# lm3410-sepic-led-driver-15mm-mk-1.net
KiCad netlist of a schematic drawn in EAGLE
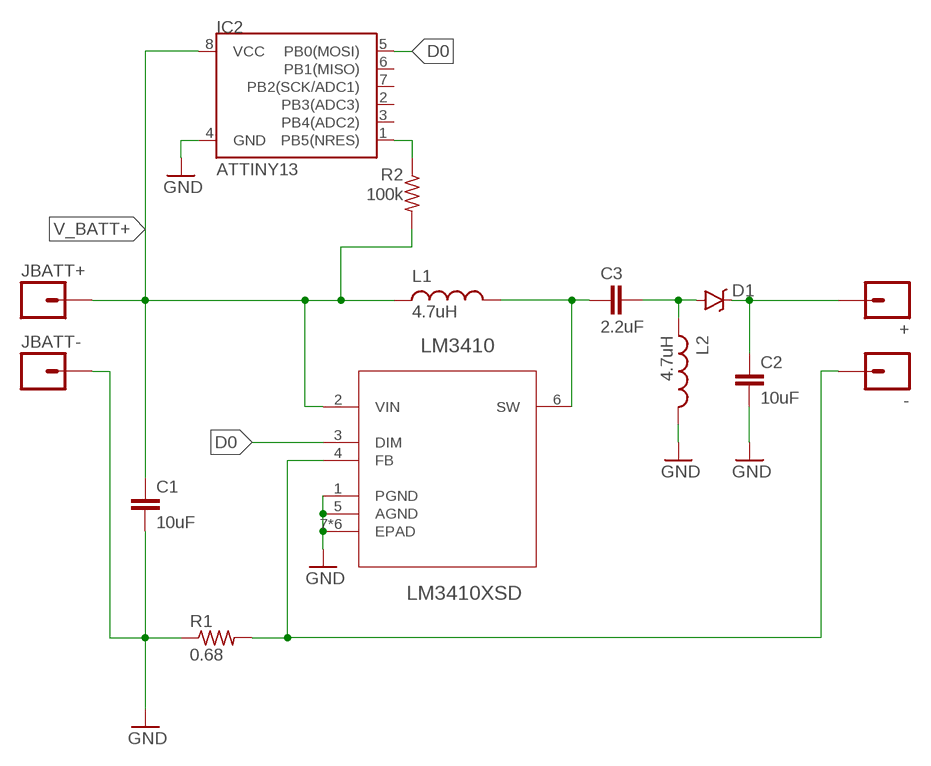
[diagram p0: schematic, sheet 1]

(export (version "E")
  (design (tool "Eeschema 10.0.6"))
  (components
    (comp (ref "+")
      (value "M01PTH-KIT")
      (footprint "eagle-import:1X01-KIT")
      (libsource (lib "eagle-import") (part "M01PTH-KIT"))
    )
    (comp (ref "-")
      (value "M01NOSILK-KIT")
      (footprint "eagle-import:1X01NS-KIT")
      (libsource (lib "eagle-import") (part "M01NOSILK-KIT"))
    )
    (comp (ref "C1")
      (value "10uF")
      (footprint "eagle-import:C0603")
      (libsource (lib "eagle-import") (part "CAPACITOR-CERAMICC0603"))
    )
    (comp (ref "C2")
      (value "10uF")
      (footprint "eagle-import:C0603")
      (libsource (lib "eagle-import") (part "CAPACITOR-CERAMICC0603"))
    )
    (comp (ref "C3")
      (value "2.2uF")
      (footprint "eagle-import:C0805")
      (libsource (lib "eagle-import") (part "CAPACITOR-CERAMICC0805"))
    )
    (comp (ref "D1")
      (value "BAT20J")
      (footprint "eagle-import:SOD-323")
      (libsource (lib "eagle-import") (part "DIODE-SCHOTTKYBAT20J"))
    )
    (comp (ref "IC2")
      (value "ATTINY13")
      (footprint "eagle-import:SO08")
      (libsource (lib "eagle-import") (part "ATTINY13SOIC"))
    )
    (comp (ref "JBATT+")
      (value "M01NOT-A-VIA-NOPE")
      (footprint "eagle-import:1X01_NOSILK_NOSTOP")
      (libsource (lib "eagle-import") (part "M01NOT-A-VIA-NOPE"))
    )
    (comp (ref "JBATT-")
      (value "M01NOT-A-VIA-NOPE")
      (footprint "eagle-import:1X01_NOSILK_NOSTOP")
      (libsource (lib "eagle-import") (part "M01NOT-A-VIA-NOPE"))
    )
    (comp (ref "L1")
      (value "4.7uH")
      (footprint "eagle-import:INDUCTOR_2X1.6MM")
      (libsource (lib "eagle-import") (part "INDUCTORIFSC-0806"))
    )
    (comp (ref "L2")
      (value "4.7uH")
      (footprint "eagle-import:INDUCTOR_2X1.6MM")
      (libsource (lib "eagle-import") (part "INDUCTORIFSC-0806"))
    )
    (comp (ref "LM3410")
      (value "LM3410XSD")
      (footprint "eagle-import:DFN300X300X80-7N")
      (libsource (lib "eagle-import") (part "LM3410XSD"))
    )
    (comp (ref "R1")
      (value "0.68")
      (footprint "eagle-import:R1206")
      (libsource (lib "eagle-import") (part "RESISTORR1206"))
    )
    (comp (ref "R2")
      (value "100k")
      (footprint "eagle-import:R0402")
      (libsource (lib "eagle-import") (part "RESISTORR0402"))
    )
  )
  (nets
    (net (code "1") (name "D0") (class "Default")
      (node (ref "IC2") (pin "5") (pinfunction "PB0(MOSI)_5") (pintype "bidirectional"))
      (node (ref "LM3410") (pin "3") (pinfunction "DIM_3") (pintype "input"))
    )
    (net (code "2") (name "GND") (class "Default")
      (node (ref "C1") (pin "2") (pinfunction "2_2") (pintype "passive"))
      (node (ref "C2") (pin "2") (pinfunction "2_2") (pintype "passive"))
      (node (ref "IC2") (pin "4") (pinfunction "GND_4") (pintype "bidirectional"))
      (node (ref "JBATT-") (pin "P$1") (pinfunction "1_P$1") (pintype "passive"))
      (node (ref "L2") (pin "P$2") (pinfunction "2_P$2") (pintype "passive"))
      (node (ref "LM3410") (pin "1") (pinfunction "PGND_1") (pintype "passive"))
      (node (ref "LM3410") (pin "5") (pinfunction "AGND_5") (pintype "passive"))
      (node (ref "LM3410") (pin "7") (pinfunction "EPAD_7") (pintype "passive"))
      (node (ref "LM3410") (pin "7@1") (pinfunction "EPAD_7@1") (pintype "passive"))
      (node (ref "LM3410") (pin "7@2") (pinfunction "EPAD_7@2") (pintype "passive"))
      (node (ref "LM3410") (pin "7@3") (pinfunction "EPAD_7@3") (pintype "passive"))
      (node (ref "LM3410") (pin "7@4") (pinfunction "EPAD_7@4") (pintype "passive"))
      (node (ref "LM3410") (pin "7@5") (pinfunction "EPAD_7@5") (pintype "passive"))
      (node (ref "R1") (pin "1") (pinfunction "1_1") (pintype "passive"))
    )
    (net (code "3") (name "Net-(+-Pad1)") (class "Default")
      (node (ref "+") (pin "1") (pinfunction "1_1") (pintype "passive"))
      (node (ref "C2") (pin "1") (pinfunction "1_1") (pintype "passive"))
      (node (ref "D1") (pin "C") (pinfunction "C_C") (pintype "passive"))
    )
    (net (code "4") (name "Net-(IC2-PB5(NRES))") (class "Default")
      (node (ref "IC2") (pin "1") (pinfunction "PB5(NRES)_1") (pintype "bidirectional"))
      (node (ref "R2") (pin "1") (pinfunction "1_1") (pintype "passive"))
    )
    (net (code "5") (name "Net-(L1-2)") (class "Default")
      (node (ref "C3") (pin "1") (pinfunction "1_1") (pintype "passive"))
      (node (ref "L1") (pin "P$2") (pinfunction "2_P$2") (pintype "passive"))
      (node (ref "LM3410") (pin "6") (pinfunction "SW_6") (pintype "output"))
    )
    (net (code "6") (name "Net-(L2-1)") (class "Default")
      (node (ref "C3") (pin "2") (pinfunction "2_2") (pintype "passive"))
      (node (ref "D1") (pin "A") (pinfunction "A_A") (pintype "passive"))
      (node (ref "L2") (pin "P$1") (pinfunction "1_P$1") (pintype "passive"))
    )
    (net (code "7") (name "Net-(LM3410-FB)") (class "Default")
      (node (ref "-") (pin "1") (pinfunction "1_1") (pintype "passive"))
      (node (ref "LM3410") (pin "4") (pinfunction "FB_4") (pintype "input"))
      (node (ref "R1") (pin "2") (pinfunction "2_2") (pintype "passive"))
    )
    (net (code "8") (name "V_BATT+") (class "Default")
      (node (ref "C1") (pin "1") (pinfunction "1_1") (pintype "passive"))
      (node (ref "IC2") (pin "8") (pinfunction "VCC_8") (pintype "bidirectional"))
      (node (ref "JBATT+") (pin "P$1") (pinfunction "1_P$1") (pintype "passive"))
      (node (ref "L1") (pin "P$1") (pinfunction "1_P$1") (pintype "passive"))
      (node (ref "LM3410") (pin "2") (pinfunction "VIN_2") (pintype "power_in"))
      (node (ref "R2") (pin "2") (pinfunction "2_2") (pintype "passive"))
    )
    (net (code "9") (name "unconnected-(IC2-PB1(MISO)-Pad6)") (class "Default")
      (node (ref "IC2") (pin "6") (pinfunction "PB1(MISO)_6") (pintype "bidirectional"))
    )
    (net (code "10") (name "unconnected-(IC2-PB2(SCK{slash}ADC1)-Pad7)") (class "Default")
      (node (ref "IC2") (pin "7") (pinfunction "PB2(SCK/ADC1)_7") (pintype "bidirectional"))
    )
    (net (code "11") (name "unconnected-(IC2-PB3(ADC3)-Pad2)") (class "Default")
      (node (ref "IC2") (pin "2") (pinfunction "PB3(ADC3)_2") (pintype "bidirectional"))
    )
    (net (code "12") (name "unconnected-(IC2-PB4(ADC2)-Pad3)") (class "Default")
      (node (ref "IC2") (pin "3") (pinfunction "PB4(ADC2)_3") (pintype "bidirectional"))
    )
  )
)
